# legacy-wing-v1.net
KiCad netlist of a schematic drawn in EAGLE
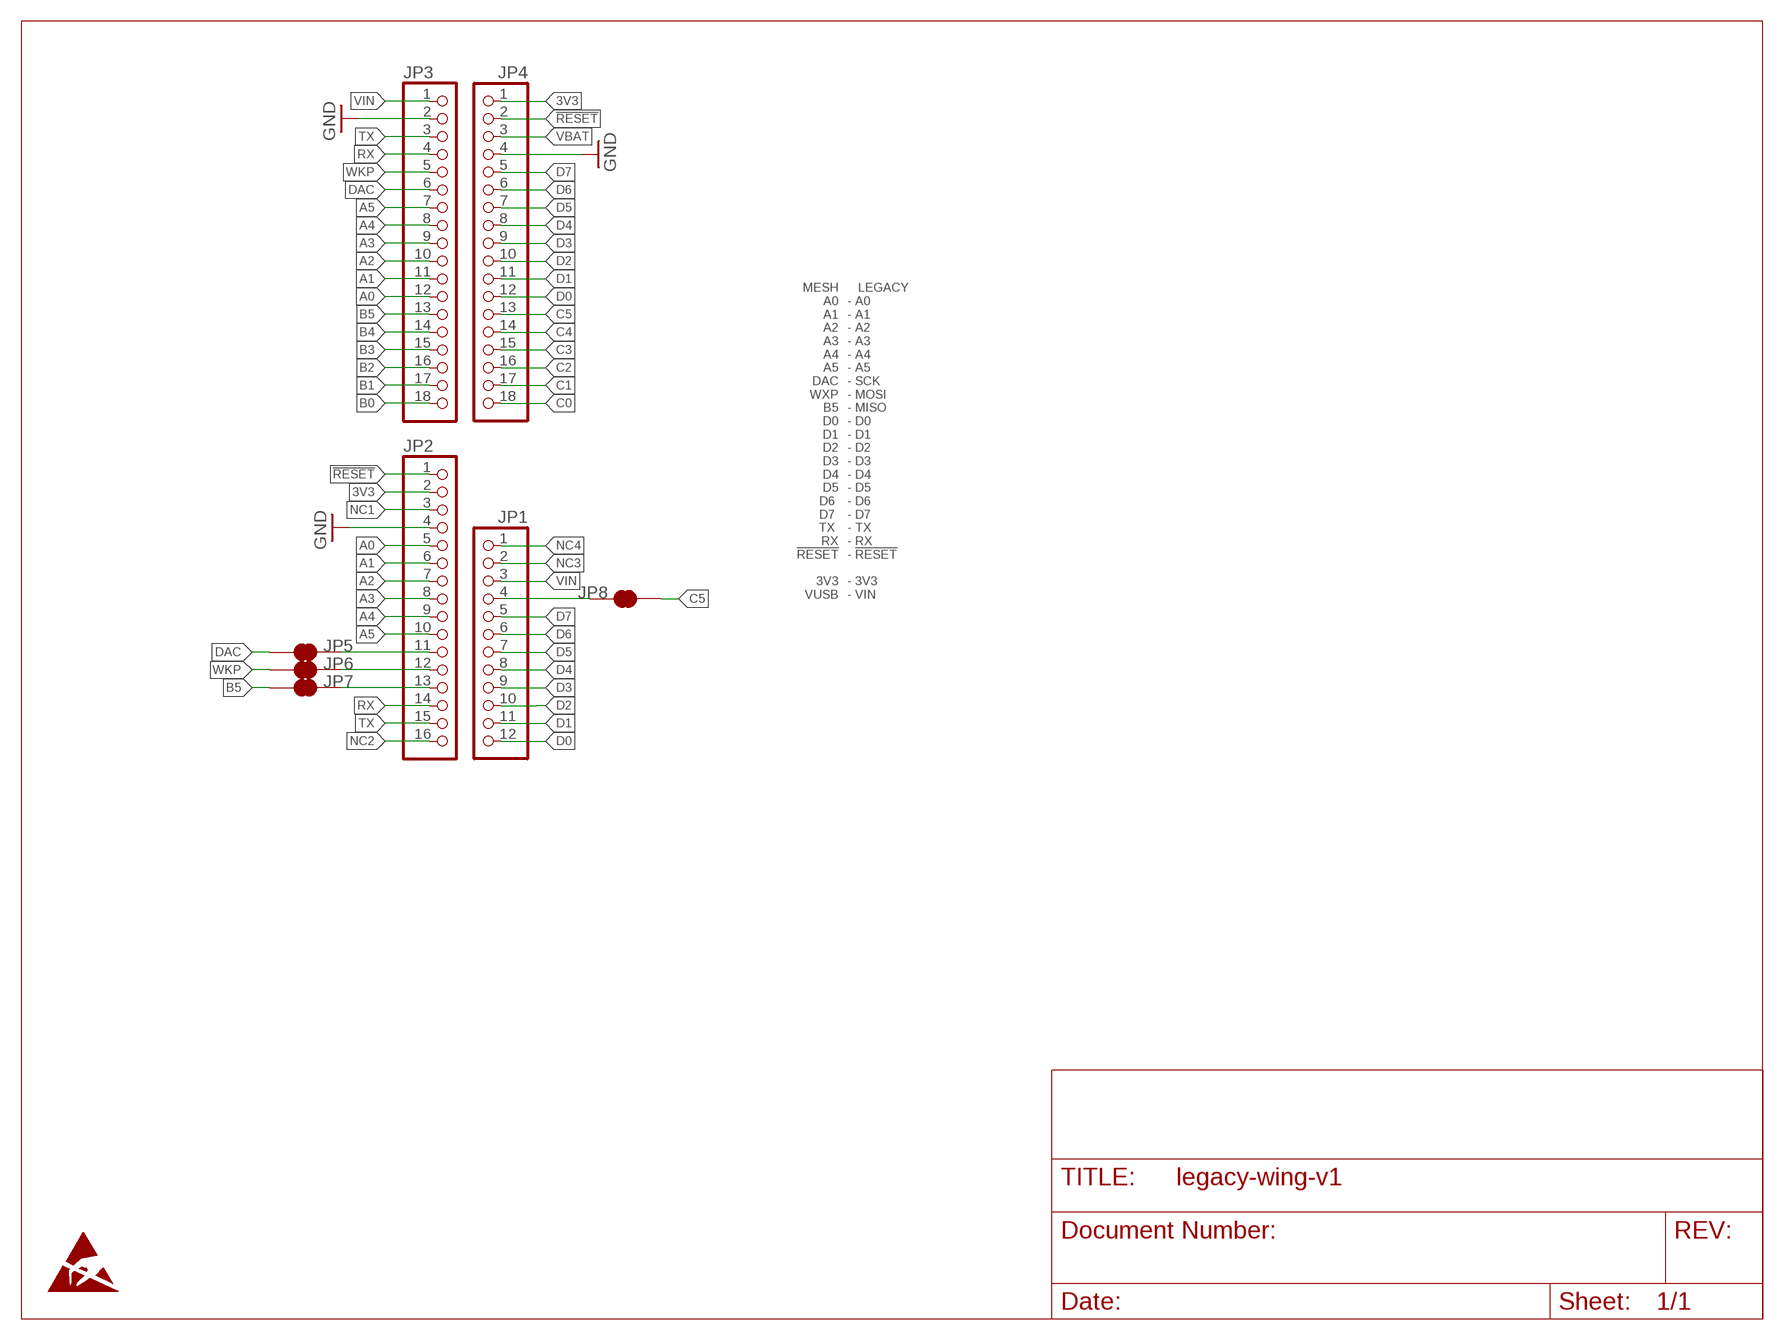
[diagram p0: schematic, sheet 1]

(export (version "E")
  (design (tool "Eeschema 10.0.6"))
  (components
    (comp (ref "JP1")
      (value "PINHD-1X121X12_SMT")
      (footprint "eagle-import:1X12_SMT")
      (libsource (lib "eagle-import") (part "PINHD-1X121X12_SMT"))
    )
    (comp (ref "JP2")
      (value "PINHD-1X161X16_SMT")
      (footprint "eagle-import:1X16_SMT")
      (libsource (lib "eagle-import") (part "PINHD-1X161X16_SMT"))
    )
    (comp (ref "JP3")
      (value "PINHD-1X181X18_SMT")
      (footprint "eagle-import:1X18_SMT")
      (libsource (lib "eagle-import") (part "PINHD-1X181X18_SMT"))
    )
    (comp (ref "JP4")
      (value "PINHD-1X181X18_SMT")
      (footprint "eagle-import:1X18_SMT")
      (libsource (lib "eagle-import") (part "PINHD-1X181X18_SMT"))
    )
    (comp (ref "JP5")
      (value "JUMPER-SMT_2_NC_TRACE_NO-SILK")
      (footprint "eagle-import:SMT-JUMPER_2_NC_TRACE_NO-SILK")
      (libsource (lib "eagle-import") (part "JUMPER-SMT_2_NC_TRACE_NO-SILK"))
    )
    (comp (ref "JP6")
      (value "JUMPER-SMT_2_NC_TRACE_NO-SILK")
      (footprint "eagle-import:SMT-JUMPER_2_NC_TRACE_NO-SILK")
      (libsource (lib "eagle-import") (part "JUMPER-SMT_2_NC_TRACE_NO-SILK"))
    )
    (comp (ref "JP7")
      (value "JUMPER-SMT_2_NC_TRACE_NO-SILK")
      (footprint "eagle-import:SMT-JUMPER_2_NC_TRACE_NO-SILK")
      (libsource (lib "eagle-import") (part "JUMPER-SMT_2_NC_TRACE_NO-SILK"))
    )
    (comp (ref "JP8")
      (value "JUMPER-SMT_2_NC_TRACE_NO-SILK")
      (footprint "eagle-import:SMT-JUMPER_2_NC_TRACE_NO-SILK")
      (libsource (lib "eagle-import") (part "JUMPER-SMT_2_NC_TRACE_NO-SILK"))
    )
  )
  (nets
    (net (code "1") (name "/~{RESET}") (class "Default")
      (node (ref "JP2") (pin "1") (pinfunction "1_1") (pintype "passive"))
      (node (ref "JP4") (pin "2") (pinfunction "2_2") (pintype "passive"))
    )
    (net (code "2") (name "3V3") (class "Default")
      (node (ref "JP2") (pin "2") (pinfunction "2_2") (pintype "passive"))
      (node (ref "JP4") (pin "1") (pinfunction "1_1") (pintype "passive"))
    )
    (net (code "3") (name "A0") (class "Default")
      (node (ref "JP2") (pin "5") (pinfunction "5_5") (pintype "passive"))
      (node (ref "JP3") (pin "12") (pinfunction "12_12") (pintype "passive"))
    )
    (net (code "4") (name "A1") (class "Default")
      (node (ref "JP2") (pin "6") (pinfunction "6_6") (pintype "passive"))
      (node (ref "JP3") (pin "11") (pinfunction "11_11") (pintype "passive"))
    )
    (net (code "5") (name "A2") (class "Default")
      (node (ref "JP2") (pin "7") (pinfunction "7_7") (pintype "passive"))
      (node (ref "JP3") (pin "10") (pinfunction "10_10") (pintype "passive"))
    )
    (net (code "6") (name "A3") (class "Default")
      (node (ref "JP2") (pin "8") (pinfunction "8_8") (pintype "passive"))
      (node (ref "JP3") (pin "9") (pinfunction "9_9") (pintype "passive"))
    )
    (net (code "7") (name "A4") (class "Default")
      (node (ref "JP2") (pin "9") (pinfunction "9_9") (pintype "passive"))
      (node (ref "JP3") (pin "8") (pinfunction "8_8") (pintype "passive"))
    )
    (net (code "8") (name "A5") (class "Default")
      (node (ref "JP2") (pin "10") (pinfunction "10_10") (pintype "passive"))
      (node (ref "JP3") (pin "7") (pinfunction "7_7") (pintype "passive"))
    )
    (net (code "9") (name "B0") (class "Default")
      (node (ref "JP3") (pin "18") (pinfunction "18_18") (pintype "passive"))
    )
    (net (code "10") (name "B1") (class "Default")
      (node (ref "JP3") (pin "17") (pinfunction "17_17") (pintype "passive"))
    )
    (net (code "11") (name "B2") (class "Default")
      (node (ref "JP3") (pin "16") (pinfunction "16_16") (pintype "passive"))
    )
    (net (code "12") (name "B3") (class "Default")
      (node (ref "JP3") (pin "15") (pinfunction "15_15") (pintype "passive"))
    )
    (net (code "13") (name "B4") (class "Default")
      (node (ref "JP3") (pin "14") (pinfunction "14_14") (pintype "passive"))
    )
    (net (code "14") (name "B5") (class "Default")
      (node (ref "JP3") (pin "13") (pinfunction "13_13") (pintype "passive"))
      (node (ref "JP7") (pin "1") (pinfunction "1_1") (pintype "passive"))
    )
    (net (code "15") (name "C0") (class "Default")
      (node (ref "JP4") (pin "18") (pinfunction "18_18") (pintype "passive"))
    )
    (net (code "16") (name "C1") (class "Default")
      (node (ref "JP4") (pin "17") (pinfunction "17_17") (pintype "passive"))
    )
    (net (code "17") (name "C2") (class "Default")
      (node (ref "JP4") (pin "16") (pinfunction "16_16") (pintype "passive"))
    )
    (net (code "18") (name "C3") (class "Default")
      (node (ref "JP4") (pin "15") (pinfunction "15_15") (pintype "passive"))
    )
    (net (code "19") (name "C4") (class "Default")
      (node (ref "JP4") (pin "14") (pinfunction "14_14") (pintype "passive"))
    )
    (net (code "20") (name "C5") (class "Default")
      (node (ref "JP4") (pin "13") (pinfunction "13_13") (pintype "passive"))
      (node (ref "JP8") (pin "2") (pinfunction "2_2") (pintype "passive"))
    )
    (net (code "21") (name "D0") (class "Default")
      (node (ref "JP1") (pin "12") (pinfunction "12_12") (pintype "passive"))
      (node (ref "JP4") (pin "12") (pinfunction "12_12") (pintype "passive"))
    )
    (net (code "22") (name "D1") (class "Default")
      (node (ref "JP1") (pin "11") (pinfunction "11_11") (pintype "passive"))
      (node (ref "JP4") (pin "11") (pinfunction "11_11") (pintype "passive"))
    )
    (net (code "23") (name "D2") (class "Default")
      (node (ref "JP1") (pin "10") (pinfunction "10_10") (pintype "passive"))
      (node (ref "JP4") (pin "10") (pinfunction "10_10") (pintype "passive"))
    )
    (net (code "24") (name "D3") (class "Default")
      (node (ref "JP1") (pin "9") (pinfunction "9_9") (pintype "passive"))
      (node (ref "JP4") (pin "9") (pinfunction "9_9") (pintype "passive"))
    )
    (net (code "25") (name "D4") (class "Default")
      (node (ref "JP1") (pin "8") (pinfunction "8_8") (pintype "passive"))
      (node (ref "JP4") (pin "8") (pinfunction "8_8") (pintype "passive"))
    )
    (net (code "26") (name "D5") (class "Default")
      (node (ref "JP1") (pin "7") (pinfunction "7_7") (pintype "passive"))
      (node (ref "JP4") (pin "7") (pinfunction "7_7") (pintype "passive"))
    )
    (net (code "27") (name "D6") (class "Default")
      (node (ref "JP1") (pin "6") (pinfunction "6_6") (pintype "passive"))
      (node (ref "JP4") (pin "6") (pinfunction "6_6") (pintype "passive"))
    )
    (net (code "28") (name "D7") (class "Default")
      (node (ref "JP1") (pin "5") (pinfunction "5_5") (pintype "passive"))
      (node (ref "JP4") (pin "5") (pinfunction "5_5") (pintype "passive"))
    )
    (net (code "29") (name "DAC") (class "Default")
      (node (ref "JP3") (pin "6") (pinfunction "6_6") (pintype "passive"))
      (node (ref "JP5") (pin "1") (pinfunction "1_1") (pintype "passive"))
    )
    (net (code "30") (name "GND") (class "Default")
      (node (ref "JP2") (pin "4") (pinfunction "4_4") (pintype "passive"))
      (node (ref "JP3") (pin "2") (pinfunction "2_2") (pintype "passive"))
      (node (ref "JP4") (pin "4") (pinfunction "4_4") (pintype "passive"))
    )
    (net (code "31") (name "NC1") (class "Default")
      (node (ref "JP2") (pin "3") (pinfunction "3_3") (pintype "passive"))
    )
    (net (code "32") (name "NC2") (class "Default")
      (node (ref "JP2") (pin "16") (pinfunction "16_16") (pintype "passive"))
    )
    (net (code "33") (name "NC3") (class "Default")
      (node (ref "JP1") (pin "2") (pinfunction "2_2") (pintype "passive"))
    )
    (net (code "34") (name "NC4") (class "Default")
      (node (ref "JP1") (pin "1") (pinfunction "1_1") (pintype "passive"))
    )
    (net (code "35") (name "Net-(JP1-Pad4)") (class "Default")
      (node (ref "JP1") (pin "4") (pinfunction "4_4") (pintype "passive"))
      (node (ref "JP8") (pin "1") (pinfunction "1_1") (pintype "passive"))
    )
    (net (code "36") (name "Net-(JP2-Pad11)") (class "Default")
      (node (ref "JP2") (pin "11") (pinfunction "11_11") (pintype "passive"))
      (node (ref "JP5") (pin "2") (pinfunction "2_2") (pintype "passive"))
    )
    (net (code "37") (name "Net-(JP2-Pad12)") (class "Default")
      (node (ref "JP2") (pin "12") (pinfunction "12_12") (pintype "passive"))
      (node (ref "JP6") (pin "2") (pinfunction "2_2") (pintype "passive"))
    )
    (net (code "38") (name "Net-(JP2-Pad13)") (class "Default")
      (node (ref "JP2") (pin "13") (pinfunction "13_13") (pintype "passive"))
      (node (ref "JP7") (pin "2") (pinfunction "2_2") (pintype "passive"))
    )
    (net (code "39") (name "RX") (class "Default")
      (node (ref "JP2") (pin "14") (pinfunction "14_14") (pintype "passive"))
      (node (ref "JP3") (pin "4") (pinfunction "4_4") (pintype "passive"))
    )
    (net (code "40") (name "TX") (class "Default")
      (node (ref "JP2") (pin "15") (pinfunction "15_15") (pintype "passive"))
      (node (ref "JP3") (pin "3") (pinfunction "3_3") (pintype "passive"))
    )
    (net (code "41") (name "VBAT") (class "Default")
      (node (ref "JP4") (pin "3") (pinfunction "3_3") (pintype "passive"))
    )
    (net (code "42") (name "VIN") (class "Default")
      (node (ref "JP1") (pin "3") (pinfunction "3_3") (pintype "passive"))
      (node (ref "JP3") (pin "1") (pinfunction "1_1") (pintype "passive"))
    )
    (net (code "43") (name "WKP") (class "Default")
      (node (ref "JP3") (pin "5") (pinfunction "5_5") (pintype "passive"))
      (node (ref "JP6") (pin "1") (pinfunction "1_1") (pintype "passive"))
    )
  )
)
